# sensor_cny70.net
KiCad netlist of a schematic drawn in EAGLE
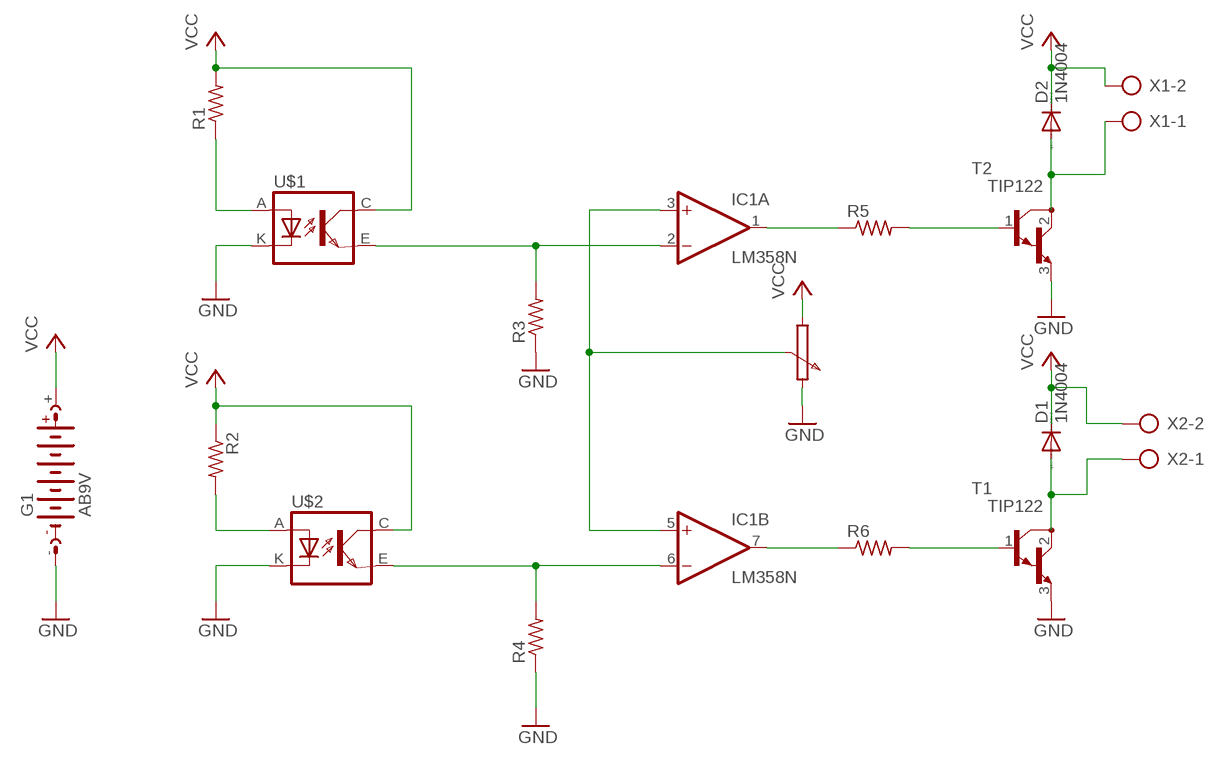
[diagram p0: schematic, sheet 1]

(export (version "E")
  (design (tool "Eeschema 10.0.6"))
  (components
    (comp (ref "D1")
      (value "1N4004")
      (footprint "eagle-import:DO41-10")
      (libsource (lib "eagle-import") (part "1N4004"))
    )
    (comp (ref "D2")
      (value "1N4004")
      (footprint "eagle-import:DO41-10")
      (libsource (lib "eagle-import") (part "1N4004"))
    )
    (comp (ref "G1")
      (value "AB9V")
      (footprint "eagle-import:AB9V")
      (libsource (lib "eagle-import") (part "AB9V"))
    )
    (comp (ref "IC1")
      (value "LM358N")
      (footprint "eagle-import:DIL08")
      (libsource (lib "eagle-import") (part "LM358N"))
    )
    (comp (ref "R1")
      (value "R-US_0207/10")
      (footprint "eagle-import:0207_10")
      (libsource (lib "eagle-import") (part "R-US_0207/10"))
    )
    (comp (ref "R2")
      (value "R-US_0207/10")
      (footprint "eagle-import:0207_10")
      (libsource (lib "eagle-import") (part "R-US_0207/10"))
    )
    (comp (ref "R3")
      (value "R-US_0207/10")
      (footprint "eagle-import:0207_10")
      (libsource (lib "eagle-import") (part "R-US_0207/10"))
    )
    (comp (ref "R4")
      (value "R-US_0207/10")
      (footprint "eagle-import:0207_10")
      (libsource (lib "eagle-import") (part "R-US_0207/10"))
    )
    (comp (ref "R5")
      (value "R-US_0207/10")
      (footprint "eagle-import:0207_10")
      (libsource (lib "eagle-import") (part "R-US_0207/10"))
    )
    (comp (ref "R6")
      (value "R-US_0207/10")
      (footprint "eagle-import:0207_10")
      (libsource (lib "eagle-import") (part "R-US_0207/10"))
    )
    (comp (ref "T1")
      (value "TIP122")
      (footprint "eagle-import:TO220")
      (libsource (lib "eagle-import") (part "TIP122"))
    )
    (comp (ref "T2")
      (value "TIP122")
      (footprint "eagle-import:TO220")
      (libsource (lib "eagle-import") (part "TIP122"))
    )
    (comp (ref "U$1")
      (value "CNY70")
      (footprint "eagle-import:4")
      (libsource (lib "eagle-import") (part "CNY70"))
    )
    (comp (ref "U$2")
      (value "CNY70")
      (footprint "eagle-import:4")
      (libsource (lib "eagle-import") (part "CNY70"))
    )
    (comp (ref "X1")
      (value "AK500/2")
      (footprint "eagle-import:AK500_2")
      (libsource (lib "eagle-import") (part "AK500/2"))
    )
    (comp (ref "X2")
      (value "AK500/2")
      (footprint "eagle-import:AK500_2")
      (libsource (lib "eagle-import") (part "AK500/2"))
    )
  )
  (nets
    (net (code "1") (name "GND") (class "Default")
      (node (ref "G1") (pin "-") (pinfunction "-_-") (pintype "passive"))
      (node (ref "R3") (pin "1") (pinfunction "1_1") (pintype "passive"))
      (node (ref "R4") (pin "1") (pinfunction "1_1") (pintype "passive"))
      (node (ref "T1") (pin "3") (pinfunction "E_3") (pintype "passive"))
      (node (ref "T2") (pin "3") (pinfunction "E_3") (pintype "passive"))
      (node (ref "U$1") (pin "K") (pinfunction "C_K") (pintype "passive"))
      (node (ref "U$2") (pin "K") (pinfunction "C_K") (pintype "passive"))
    )
    (net (code "2") (name "Net-(IC1A-+IN)") (class "Default")
      (node (ref "IC1") (pin "3") (pinfunction "+IN_3") (pintype "input"))
      (node (ref "IC1") (pin "5") (pinfunction "+IN_5") (pintype "input"))
    )
    (net (code "3") (name "Net-(IC1A--IN)") (class "Default")
      (node (ref "IC1") (pin "2") (pinfunction "-IN_2") (pintype "input"))
      (node (ref "R3") (pin "2") (pinfunction "2_2") (pintype "passive"))
      (node (ref "U$1") (pin "E") (pinfunction "EMI_E") (pintype "passive"))
    )
    (net (code "4") (name "Net-(IC1A-OUT)") (class "Default")
      (node (ref "IC1") (pin "1") (pinfunction "OUT_1") (pintype "output"))
      (node (ref "R5") (pin "1") (pinfunction "1_1") (pintype "passive"))
    )
    (net (code "5") (name "Net-(IC1B--IN)") (class "Default")
      (node (ref "IC1") (pin "6") (pinfunction "-IN_6") (pintype "input"))
      (node (ref "R4") (pin "2") (pinfunction "2_2") (pintype "passive"))
      (node (ref "U$2") (pin "E") (pinfunction "EMI_E") (pintype "passive"))
    )
    (net (code "6") (name "Net-(IC1B-OUT)") (class "Default")
      (node (ref "IC1") (pin "7") (pinfunction "OUT_7") (pintype "output"))
      (node (ref "R6") (pin "1") (pinfunction "1_1") (pintype "passive"))
    )
    (net (code "7") (name "Net-(R1-Pad1)") (class "Default")
      (node (ref "R1") (pin "1") (pinfunction "1_1") (pintype "passive"))
      (node (ref "U$1") (pin "A") (pinfunction "A_A") (pintype "passive"))
    )
    (net (code "8") (name "Net-(R2-Pad2)") (class "Default")
      (node (ref "R2") (pin "2") (pinfunction "2_2") (pintype "passive"))
      (node (ref "U$2") (pin "A") (pinfunction "A_A") (pintype "passive"))
    )
    (net (code "9") (name "Net-(T1-B)") (class "Default")
      (node (ref "R6") (pin "2") (pinfunction "2_2") (pintype "passive"))
      (node (ref "T1") (pin "1") (pinfunction "B_1") (pintype "passive"))
    )
    (net (code "10") (name "Net-(T1-C)") (class "Default")
      (node (ref "D1") (pin "A") (pinfunction "A_A") (pintype "passive"))
      (node (ref "T1") (pin "2") (pinfunction "C_2") (pintype "passive"))
      (node (ref "X2") (pin "1") (pinfunction "KL_1") (pintype "passive"))
    )
    (net (code "11") (name "Net-(T2-B)") (class "Default")
      (node (ref "R5") (pin "2") (pinfunction "2_2") (pintype "passive"))
      (node (ref "T2") (pin "1") (pinfunction "B_1") (pintype "passive"))
    )
    (net (code "12") (name "Net-(T2-C)") (class "Default")
      (node (ref "D2") (pin "A") (pinfunction "A_A") (pintype "passive"))
      (node (ref "T2") (pin "2") (pinfunction "C_2") (pintype "passive"))
      (node (ref "X1") (pin "1") (pinfunction "KL_1") (pintype "passive"))
    )
    (net (code "13") (name "VCC") (class "Default")
      (node (ref "D1") (pin "C") (pinfunction "C_C") (pintype "passive"))
      (node (ref "D2") (pin "C") (pinfunction "C_C") (pintype "passive"))
      (node (ref "G1") (pin "+") (pinfunction "+_+") (pintype "passive"))
      (node (ref "R1") (pin "2") (pinfunction "2_2") (pintype "passive"))
      (node (ref "R2") (pin "1") (pinfunction "1_1") (pintype "passive"))
      (node (ref "U$1") (pin "C") (pinfunction "COL_C") (pintype "passive"))
      (node (ref "U$2") (pin "C") (pinfunction "COL_C") (pintype "passive"))
      (node (ref "X1") (pin "2") (pinfunction "KL_2") (pintype "passive"))
      (node (ref "X2") (pin "2") (pinfunction "KL_2") (pintype "passive"))
    )
  )
)
